# ESP32.net
KiCad netlist of a schematic drawn in Altium Designer
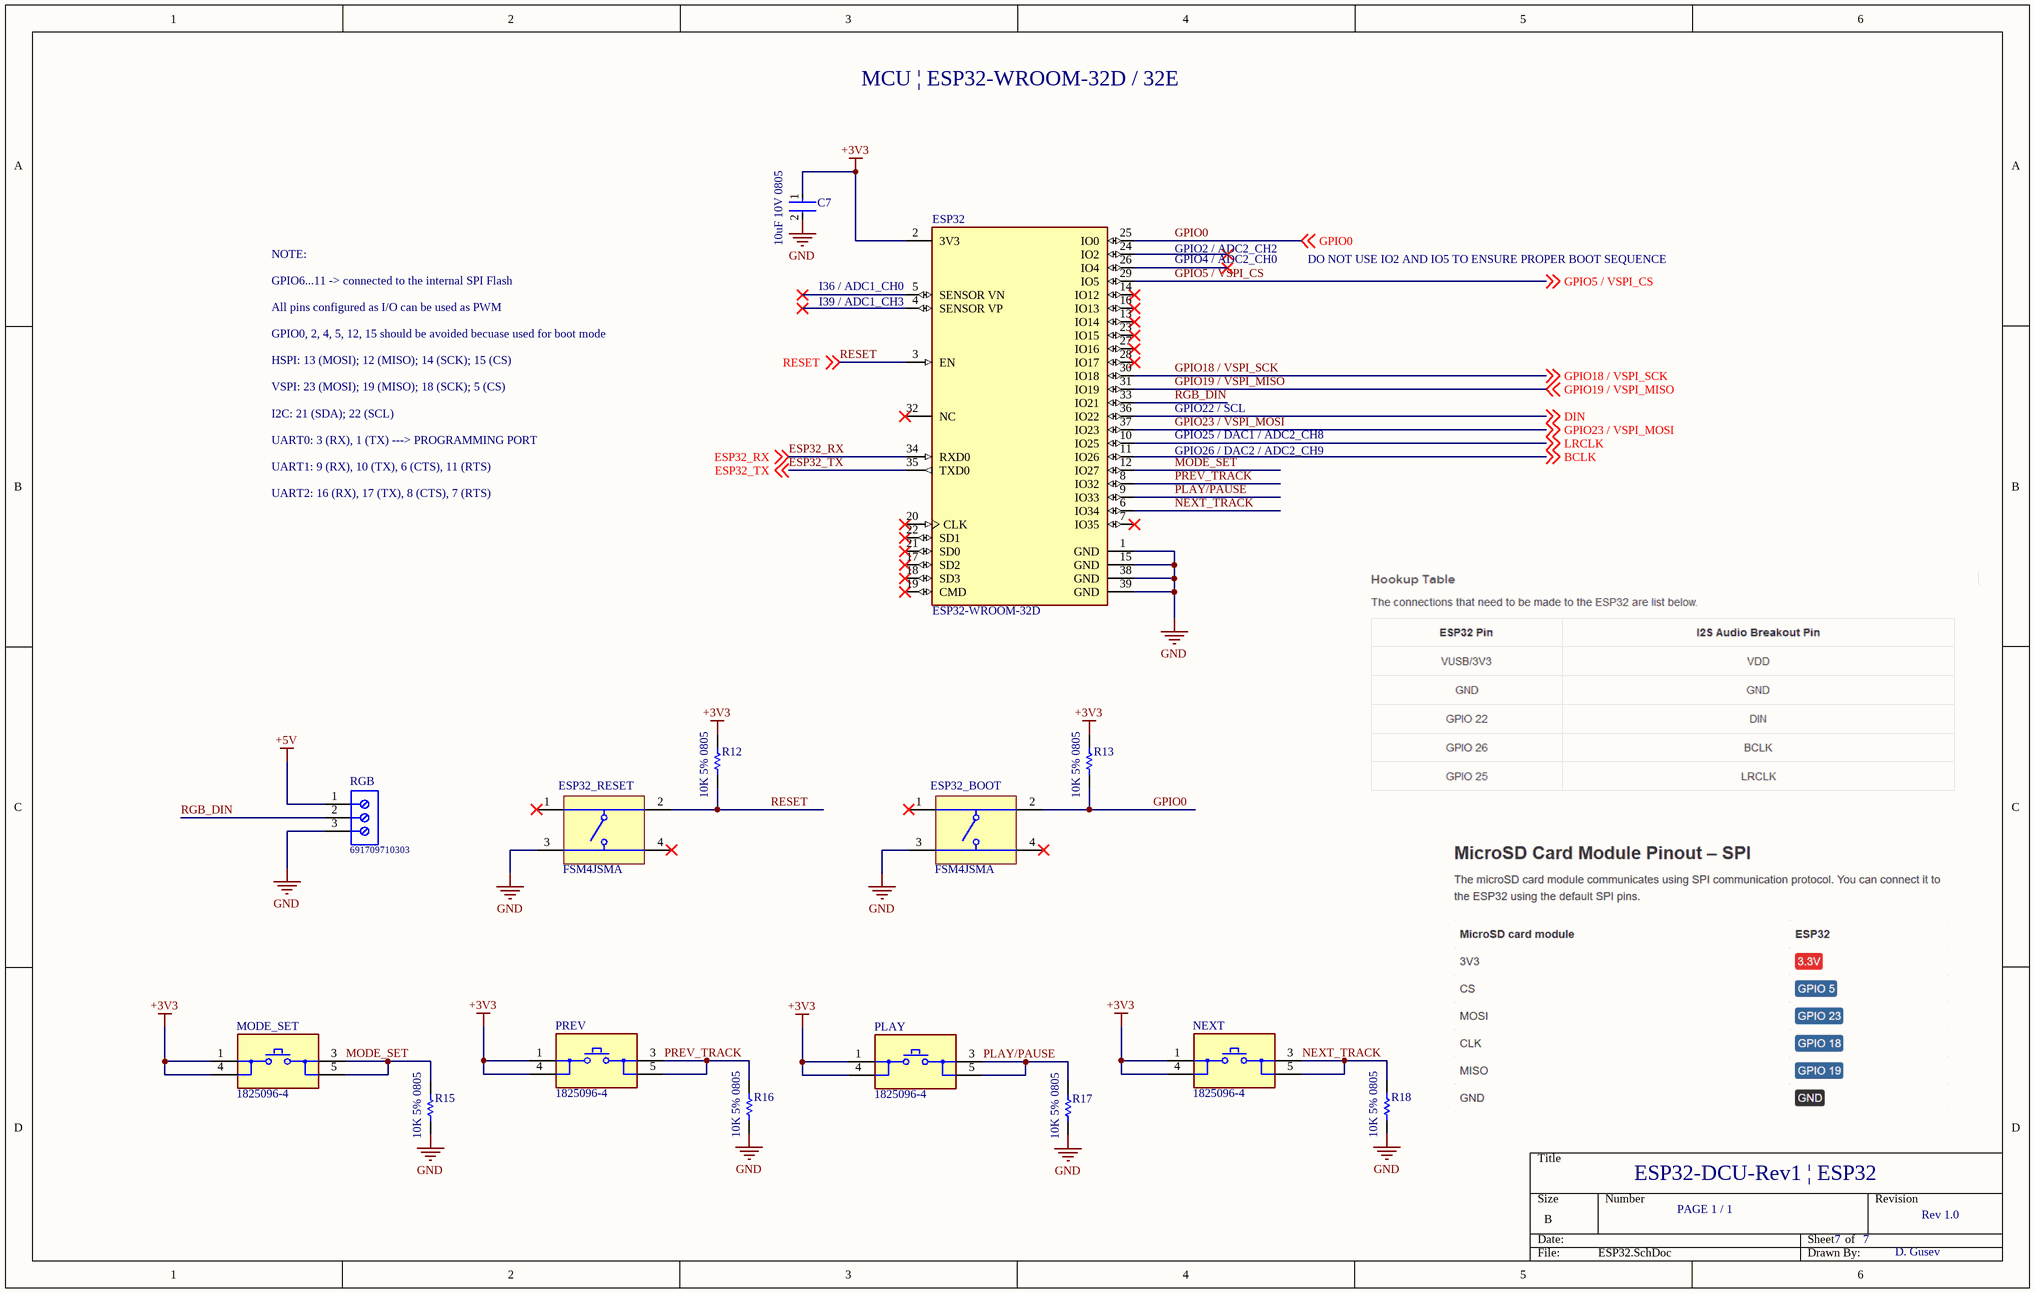
[diagram p0: ESP32.SchDoc]

(export (version "E")
  (design (tool "Eeschema 10.0.6"))
  (components
    (comp (ref "C7")
      (value "10uF 10V 0805")
      (footprint "FP-C0805C-DG-MFG")
      (description "CAP CER 10UF 10V X5R 0805")
      (fields (field (name "TOLERANCE") "10%") (field (name "MANUFACTURER PART NUMBER") "C0805C106K8PACTU"))
      (libsource (lib "Altium Content Vault") (part "11868f565c42a9108669ba33697ecf6"))
    )
    (comp (ref "ESP32")
      (value "ESP32-WROOM-32D")
      (footprint "FP-ESP32-WROOM-32D-MFG")
      (description "WIFI MODULE 32MBITS SPI FLASH")
      (fields
        (field (name "OCTOPART") "https://octopart.com/esp32-wroom-32d-espressif+systems-91040050")
        (field (name "MANUFACTURER") "Espressif Systems")
      )
      (libsource (lib "Altium Content Vault") (part "a031a76f8c27026a7a7f4657ff233a3"))
    )
    (comp (ref "ESP32_BOOT")
      (value "FSM4JSMA")
      (footprint "TECO-FSM4JSMA_V")
      (description "Swicth, SPST, 24 V, -35 to 85 degC, 4-Pin SMD, RoHS, Tape and Reel")
      (fields (field (name "MANUFACTURER") "TE Connectivity"))
      (libsource (lib "Altium Content Vault") (part "SW-SPST-4_A"))
    )
    (comp (ref "ESP32_RESET")
      (value "FSM4JSMA")
      (footprint "TECO-FSM4JSMA_V")
      (description "Swicth, SPST, 24 V, -35 to 85 degC, 4-Pin SMD, RoHS, Tape and Reel")
      (fields (field (name "MANUFACTURER") "TE Connectivity"))
      (libsource (lib "Altium Content Vault") (part "SW-SPST-4_A"))
    )
    (comp (ref "MODE_SET")
      (value "1825096-4")
      (footprint "FP-1825096-4-MFG")
      (description "SWITCH PUSH SPST-NO 0.4VA 20V")
      (libsource (lib "Altium Content Vault") (part "a3001af468fd19008bbabfbb1fd4fd9"))
    )
    (comp (ref "NEXT")
      (value "1825096-4")
      (footprint "FP-1825096-4-MFG")
      (description "SWITCH PUSH SPST-NO 0.4VA 20V")
      (libsource (lib "Altium Content Vault") (part "a3001af468fd19008bbabfbb1fd4fd9"))
    )
    (comp (ref "PLAY")
      (value "1825096-4")
      (footprint "FP-1825096-4-MFG")
      (description "SWITCH PUSH SPST-NO 0.4VA 20V")
      (libsource (lib "Altium Content Vault") (part "a3001af468fd19008bbabfbb1fd4fd9"))
    )
    (comp (ref "PREV")
      (value "1825096-4")
      (footprint "FP-1825096-4-MFG")
      (description "SWITCH PUSH SPST-NO 0.4VA 20V")
      (libsource (lib "Altium Content Vault") (part "a3001af468fd19008bbabfbb1fd4fd9"))
    )
    (comp (ref "R12")
      (value "10K 5% 0805")
      (footprint "RESC2013X60X40ML20T25")
      (fields (field (name "PART NUMBER") "ERA6AEB123V") (field (name "MANUFACTURER") "Panasonic"))
      (libsource (lib "Altium Content Vault") (part "RES"))
    )
    (comp (ref "R13")
      (value "10K 5% 0805")
      (footprint "RESC2013X60X40ML20T25")
      (fields (field (name "PART NUMBER") "ERA6AEB123V") (field (name "MANUFACTURER") "Panasonic"))
      (libsource (lib "Altium Content Vault") (part "RES"))
    )
    (comp (ref "R15")
      (value "10K 5% 0805")
      (footprint "RESC2013X60X40ML20T25")
      (fields (field (name "PART NUMBER") "ERA6AEB123V") (field (name "MANUFACTURER") "Panasonic"))
      (libsource (lib "Altium Content Vault") (part "RES"))
    )
    (comp (ref "R16")
      (value "10K 5% 0805")
      (footprint "RESC2013X60X40ML20T25")
      (fields (field (name "PART NUMBER") "ERA6AEB123V") (field (name "MANUFACTURER") "Panasonic"))
      (libsource (lib "Altium Content Vault") (part "RES"))
    )
    (comp (ref "R17")
      (value "10K 5% 0805")
      (footprint "RESC2013X60X40ML20T25")
      (fields (field (name "PART NUMBER") "ERA6AEB123V") (field (name "MANUFACTURER") "Panasonic"))
      (libsource (lib "Altium Content Vault") (part "RES"))
    )
    (comp (ref "R18")
      (value "10K 5% 0805")
      (footprint "RESC2013X60X40ML20T25")
      (fields (field (name "PART NUMBER") "ERA6AEB123V") (field (name "MANUFACTURER") "Panasonic"))
      (libsource (lib "Altium Content Vault") (part "RES"))
    )
    (comp (ref "RGB")
      (value "691709710303")
      (footprint "691709710303")
      (description "Serie 7097 - 5.00 mm Horizontal Entry SMT with Pressure Clamp WR-TBL, 3 pin")
      (fields (field (name "MANUFACTURER") "Wurth Elektronik") (field (name "PUBLISHER") "WurthElektronik"))
      (libsource (lib "Altium Content Vault") (part "WE-CN-1P-F-TB3"))
    )
  )
  (nets
    (net (code "1") (name "+3V3") (class "Default")
      (node (ref "C7") (pin "1") (pinfunction "1_1") (pintype "passive"))
      (node (ref "ESP32") (pin "2") (pinfunction "3V3_2") (pintype "power_in"))
      (node (ref "MODE_SET") (pin "1") (pinfunction "1_1") (pintype "passive"))
      (node (ref "MODE_SET") (pin "4") (pinfunction "4_4") (pintype "passive"))
      (node (ref "NEXT") (pin "1") (pinfunction "1_1") (pintype "passive"))
      (node (ref "NEXT") (pin "4") (pinfunction "4_4") (pintype "passive"))
      (node (ref "PLAY") (pin "1") (pinfunction "1_1") (pintype "passive"))
      (node (ref "PLAY") (pin "4") (pinfunction "4_4") (pintype "passive"))
      (node (ref "PREV") (pin "1") (pinfunction "1_1") (pintype "passive"))
      (node (ref "PREV") (pin "4") (pinfunction "4_4") (pintype "passive"))
      (node (ref "R12") (pin "2") (pinfunction "2_2") (pintype "passive"))
      (node (ref "R13") (pin "2") (pinfunction "2_2") (pintype "passive"))
    )
    (net (code "2") (name "+5V") (class "Default")
      (node (ref "RGB") (pin "1") (pinfunction "1_1") (pintype "passive"))
    )
    (net (code "3") (name "/MODE_SET") (class "Default")
      (node (ref "ESP32") (pin "12") (pinfunction "IO27_12") (pintype "bidirectional"))
      (node (ref "MODE_SET") (pin "3") (pinfunction "3_3") (pintype "passive"))
      (node (ref "MODE_SET") (pin "5") (pinfunction "5_5") (pintype "passive"))
      (node (ref "R15") (pin "2") (pinfunction "2_2") (pintype "passive"))
    )
    (net (code "4") (name "/NEXT_TRACK") (class "Default")
      (node (ref "ESP32") (pin "6") (pinfunction "IO34_6") (pintype "bidirectional"))
      (node (ref "NEXT") (pin "3") (pinfunction "3_3") (pintype "passive"))
      (node (ref "NEXT") (pin "5") (pinfunction "5_5") (pintype "passive"))
      (node (ref "R18") (pin "2") (pinfunction "2_2") (pintype "passive"))
    )
    (net (code "5") (name "/PLAY{slash}PAUSE") (class "Default")
      (node (ref "ESP32") (pin "9") (pinfunction "IO33_9") (pintype "bidirectional"))
      (node (ref "PLAY") (pin "3") (pinfunction "3_3") (pintype "passive"))
      (node (ref "PLAY") (pin "5") (pinfunction "5_5") (pintype "passive"))
      (node (ref "R17") (pin "2") (pinfunction "2_2") (pintype "passive"))
    )
    (net (code "6") (name "/PREV_TRACK") (class "Default")
      (node (ref "ESP32") (pin "8") (pinfunction "IO32_8") (pintype "bidirectional"))
      (node (ref "PREV") (pin "3") (pinfunction "3_3") (pintype "passive"))
      (node (ref "PREV") (pin "5") (pinfunction "5_5") (pintype "passive"))
      (node (ref "R16") (pin "2") (pinfunction "2_2") (pintype "passive"))
    )
    (net (code "7") (name "/RGB_DIN") (class "Default")
      (node (ref "ESP32") (pin "33") (pinfunction "IO21_33") (pintype "bidirectional"))
      (node (ref "RGB") (pin "2") (pinfunction "2_2") (pintype "passive"))
    )
    (net (code "8") (name "BCLK") (class "Default")
      (node (ref "ESP32") (pin "11") (pinfunction "IO26_11") (pintype "bidirectional"))
    )
    (net (code "9") (name "DIN") (class "Default")
      (node (ref "ESP32") (pin "36") (pinfunction "IO22_36") (pintype "bidirectional"))
    )
    (net (code "10") (name "ESP32_RX") (class "Default")
      (node (ref "ESP32") (pin "34") (pinfunction "RXD0_34") (pintype "input"))
    )
    (net (code "11") (name "ESP32_TX") (class "Default")
      (node (ref "ESP32") (pin "35") (pinfunction "TXD0_35") (pintype "output"))
    )
    (net (code "12") (name "GND") (class "Default")
      (node (ref "C7") (pin "2") (pinfunction "2_2") (pintype "passive"))
      (node (ref "ESP32") (pin "1") (pinfunction "GND_1") (pintype "power_in"))
      (node (ref "ESP32") (pin "15") (pinfunction "GND_15") (pintype "power_in"))
      (node (ref "ESP32") (pin "38") (pinfunction "GND_38") (pintype "power_in"))
      (node (ref "ESP32") (pin "39") (pinfunction "GND_39") (pintype "power_in"))
      (node (ref "ESP32_BOOT") (pin "3") (pinfunction "3_3") (pintype "passive"))
      (node (ref "ESP32_RESET") (pin "3") (pinfunction "3_3") (pintype "passive"))
      (node (ref "R15") (pin "1") (pinfunction "1_1") (pintype "passive"))
      (node (ref "R16") (pin "1") (pinfunction "1_1") (pintype "passive"))
      (node (ref "R17") (pin "1") (pinfunction "1_1") (pintype "passive"))
      (node (ref "R18") (pin "1") (pinfunction "1_1") (pintype "passive"))
      (node (ref "RGB") (pin "3") (pinfunction "3_3") (pintype "passive"))
    )
    (net (code "13") (name "GPIO0") (class "Default")
      (node (ref "ESP32") (pin "25") (pinfunction "IO0_25") (pintype "bidirectional"))
      (node (ref "ESP32_BOOT") (pin "2") (pinfunction "2_2") (pintype "passive"))
      (node (ref "R13") (pin "1") (pinfunction "1_1") (pintype "passive"))
    )
    (net (code "14") (name "GPIO5 {slash} VSPI_CS") (class "Default")
      (node (ref "ESP32") (pin "29") (pinfunction "IO5_29") (pintype "bidirectional"))
    )
    (net (code "15") (name "GPIO18 {slash} VSPI_SCK") (class "Default")
      (node (ref "ESP32") (pin "30") (pinfunction "IO18_30") (pintype "bidirectional"))
    )
    (net (code "16") (name "GPIO19 {slash} VSPI_MISO") (class "Default")
      (node (ref "ESP32") (pin "31") (pinfunction "IO19_31") (pintype "bidirectional"))
    )
    (net (code "17") (name "GPIO23 {slash} VSPI_MOSI") (class "Default")
      (node (ref "ESP32") (pin "37") (pinfunction "IO23_37") (pintype "bidirectional"))
    )
    (net (code "18") (name "LRCLK") (class "Default")
      (node (ref "ESP32") (pin "10") (pinfunction "IO25_10") (pintype "bidirectional"))
    )
    (net (code "19") (name "RESET") (class "Default")
      (node (ref "ESP32") (pin "3") (pinfunction "EN_3") (pintype "input"))
      (node (ref "ESP32_RESET") (pin "2") (pinfunction "2_2") (pintype "passive"))
      (node (ref "R12") (pin "1") (pinfunction "1_1") (pintype "passive"))
    )
    (net (code "20") (name "unconnected-(ESP32-CLK-Pad20)") (class "Default")
      (node (ref "ESP32") (pin "20") (pinfunction "CLK_20") (pintype "input+no_connect"))
    )
    (net (code "21") (name "unconnected-(ESP32-CMD-Pad19)") (class "Default")
      (node (ref "ESP32") (pin "19") (pinfunction "CMD_19") (pintype "bidirectional+no_connect"))
    )
    (net (code "22") (name "unconnected-(ESP32-IO2-Pad24)") (class "Default")
      (node (ref "ESP32") (pin "24") (pinfunction "IO2_24") (pintype "bidirectional+no_connect"))
    )
    (net (code "23") (name "unconnected-(ESP32-IO4-Pad26)") (class "Default")
      (node (ref "ESP32") (pin "26") (pinfunction "IO4_26") (pintype "bidirectional+no_connect"))
    )
    (net (code "24") (name "unconnected-(ESP32-IO12-Pad14)") (class "Default")
      (node (ref "ESP32") (pin "14") (pinfunction "IO12_14") (pintype "bidirectional+no_connect"))
    )
    (net (code "25") (name "unconnected-(ESP32-IO13-Pad16)") (class "Default")
      (node (ref "ESP32") (pin "16") (pinfunction "IO13_16") (pintype "bidirectional+no_connect"))
    )
    (net (code "26") (name "unconnected-(ESP32-IO14-Pad13)") (class "Default")
      (node (ref "ESP32") (pin "13") (pinfunction "IO14_13") (pintype "bidirectional+no_connect"))
    )
    (net (code "27") (name "unconnected-(ESP32-IO15-Pad23)") (class "Default")
      (node (ref "ESP32") (pin "23") (pinfunction "IO15_23") (pintype "bidirectional+no_connect"))
    )
    (net (code "28") (name "unconnected-(ESP32-IO16-Pad27)") (class "Default")
      (node (ref "ESP32") (pin "27") (pinfunction "IO16_27") (pintype "bidirectional+no_connect"))
    )
    (net (code "29") (name "unconnected-(ESP32-IO17-Pad28)") (class "Default")
      (node (ref "ESP32") (pin "28") (pinfunction "IO17_28") (pintype "bidirectional+no_connect"))
    )
    (net (code "30") (name "unconnected-(ESP32-IO35-Pad7)") (class "Default")
      (node (ref "ESP32") (pin "7") (pinfunction "IO35_7") (pintype "bidirectional+no_connect"))
    )
    (net (code "31") (name "unconnected-(ESP32-NC-Pad32)") (class "Default")
      (node (ref "ESP32") (pin "32") (pinfunction "NC_32") (pintype "passive+no_connect"))
    )
    (net (code "32") (name "unconnected-(ESP32-SD0-Pad21)") (class "Default")
      (node (ref "ESP32") (pin "21") (pinfunction "SD0_21") (pintype "bidirectional+no_connect"))
    )
    (net (code "33") (name "unconnected-(ESP32-SD1-Pad22)") (class "Default")
      (node (ref "ESP32") (pin "22") (pinfunction "SD1_22") (pintype "bidirectional+no_connect"))
    )
    (net (code "34") (name "unconnected-(ESP32-SD2-Pad17)") (class "Default")
      (node (ref "ESP32") (pin "17") (pinfunction "SD2_17") (pintype "bidirectional+no_connect"))
    )
    (net (code "35") (name "unconnected-(ESP32-SD3-Pad18)") (class "Default")
      (node (ref "ESP32") (pin "18") (pinfunction "SD3_18") (pintype "bidirectional+no_connect"))
    )
    (net (code "36") (name "unconnected-(ESP32-SENSOR_VN-Pad5)") (class "Default")
      (node (ref "ESP32") (pin "5") (pinfunction "SENSOR_VN_5") (pintype "bidirectional+no_connect"))
    )
    (net (code "37") (name "unconnected-(ESP32-SENSOR_VP-Pad4)") (class "Default")
      (node (ref "ESP32") (pin "4") (pinfunction "SENSOR_VP_4") (pintype "bidirectional+no_connect"))
    )
    (net (code "38") (name "unconnected-(ESP32_BOOT-Pad1)") (class "Default")
      (node (ref "ESP32_BOOT") (pin "1") (pinfunction "1_1") (pintype "passive+no_connect"))
    )
    (net (code "39") (name "unconnected-(ESP32_BOOT-Pad4)") (class "Default")
      (node (ref "ESP32_BOOT") (pin "4") (pinfunction "4_4") (pintype "passive+no_connect"))
    )
    (net (code "40") (name "unconnected-(ESP32_RESET-Pad1)") (class "Default")
      (node (ref "ESP32_RESET") (pin "1") (pinfunction "1_1") (pintype "passive+no_connect"))
    )
    (net (code "41") (name "unconnected-(ESP32_RESET-Pad4)") (class "Default")
      (node (ref "ESP32_RESET") (pin "4") (pinfunction "4_4") (pintype "passive+no_connect"))
    )
  )
)
